# i2c_air_temp_humi_ds18b20_hw2_0.net
KiCad netlist of a schematic drawn in EAGLE
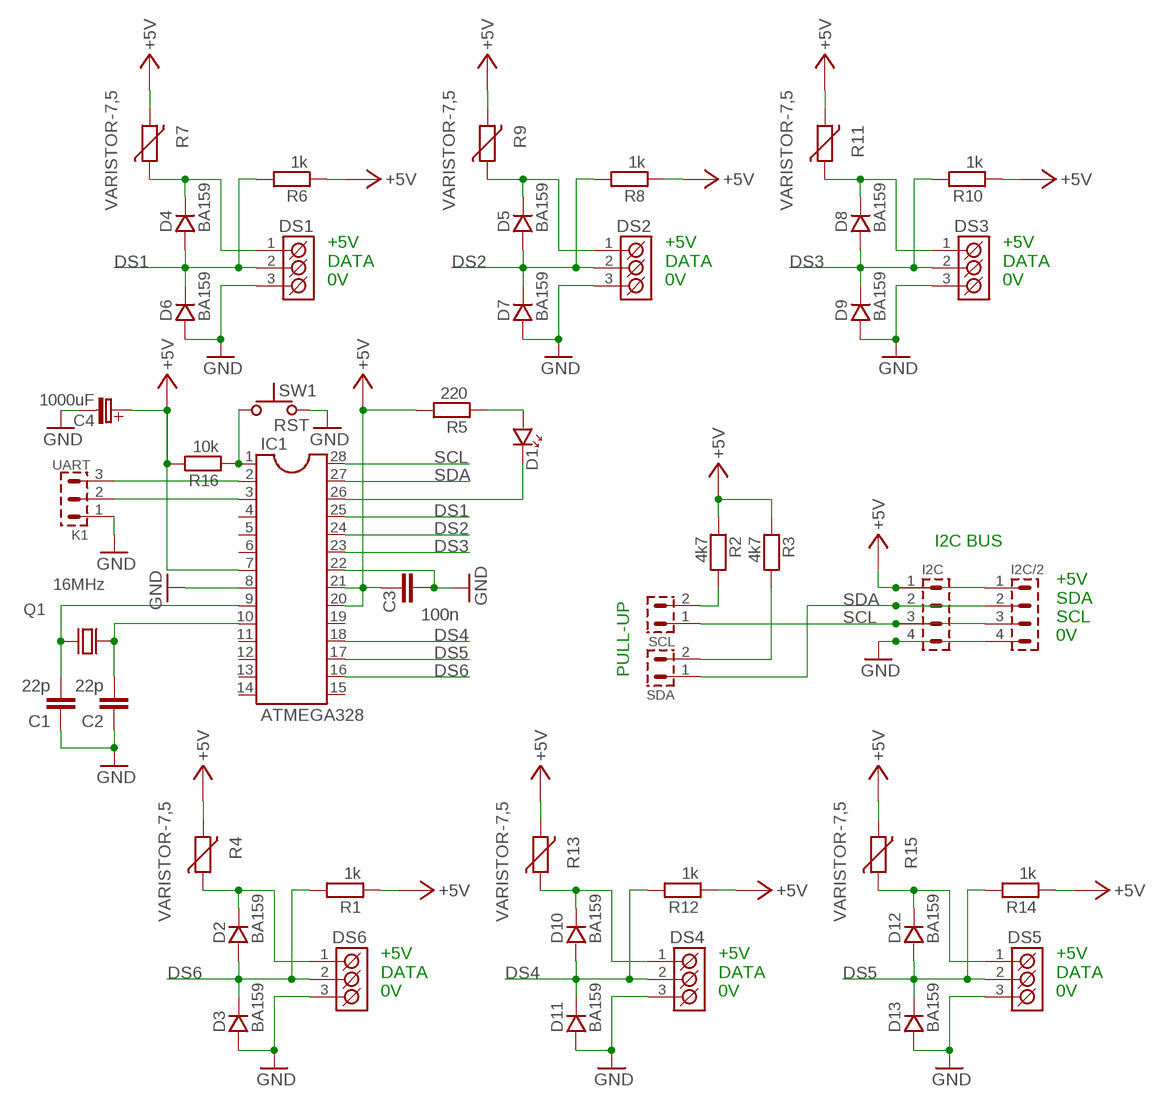
[diagram p0: schematic, sheet 1]

(export (version "E")
  (design (tool "Eeschema 10.0.6"))
  (components
    (comp (ref "C1")
      (value "22p")
      (footprint "eagle-import:C5B3")
      (libsource (lib "eagle-import") (part "C5/3"))
    )
    (comp (ref "C2")
      (value "22p")
      (footprint "eagle-import:C5B3")
      (libsource (lib "eagle-import") (part "C5/3"))
    )
    (comp (ref "C3")
      (value "100n")
      (footprint "eagle-import:C5B3")
      (libsource (lib "eagle-import") (part "C5/3"))
    )
    (comp (ref "C4")
      (value "1000uF")
      (footprint "eagle-import:C-EL_5")
      (libsource (lib "eagle-import") (part "C-EL_5"))
    )
    (comp (ref "D1")
      (value "LED_3")
      (footprint "eagle-import:LED_3")
      (libsource (lib "eagle-import") (part "LED_3"))
    )
    (comp (ref "D2")
      (value "BA159")
      (footprint "eagle-import:DO41")
      (libsource (lib "eagle-import") (part "BA159"))
    )
    (comp (ref "D3")
      (value "BA159")
      (footprint "eagle-import:DO41")
      (libsource (lib "eagle-import") (part "BA159"))
    )
    (comp (ref "D4")
      (value "BA159")
      (footprint "eagle-import:DO41")
      (libsource (lib "eagle-import") (part "BA159"))
    )
    (comp (ref "D5")
      (value "BA159")
      (footprint "eagle-import:DO41")
      (libsource (lib "eagle-import") (part "BA159"))
    )
    (comp (ref "D6")
      (value "BA159")
      (footprint "eagle-import:DO41")
      (libsource (lib "eagle-import") (part "BA159"))
    )
    (comp (ref "D7")
      (value "BA159")
      (footprint "eagle-import:DO41")
      (libsource (lib "eagle-import") (part "BA159"))
    )
    (comp (ref "D8")
      (value "BA159")
      (footprint "eagle-import:DO41")
      (libsource (lib "eagle-import") (part "BA159"))
    )
    (comp (ref "D9")
      (value "BA159")
      (footprint "eagle-import:DO41")
      (libsource (lib "eagle-import") (part "BA159"))
    )
    (comp (ref "D10")
      (value "BA159")
      (footprint "eagle-import:DO41")
      (libsource (lib "eagle-import") (part "BA159"))
    )
    (comp (ref "D11")
      (value "BA159")
      (footprint "eagle-import:DO41")
      (libsource (lib "eagle-import") (part "BA159"))
    )
    (comp (ref "D12")
      (value "BA159")
      (footprint "eagle-import:DO41")
      (libsource (lib "eagle-import") (part "BA159"))
    )
    (comp (ref "D13")
      (value "BA159")
      (footprint "eagle-import:DO41")
      (libsource (lib "eagle-import") (part "BA159"))
    )
    (comp (ref "DS1")
      (value "ARK500/3")
      (footprint "eagle-import:ARK500_3")
      (libsource (lib "eagle-import") (part "ARK500/3"))
    )
    (comp (ref "DS2")
      (value "ARK500/3")
      (footprint "eagle-import:ARK500_3")
      (libsource (lib "eagle-import") (part "ARK500/3"))
    )
    (comp (ref "DS3")
      (value "ARK500/3")
      (footprint "eagle-import:ARK500_3")
      (libsource (lib "eagle-import") (part "ARK500/3"))
    )
    (comp (ref "DS4")
      (value "ARK500/3")
      (footprint "eagle-import:ARK500_3")
      (libsource (lib "eagle-import") (part "ARK500/3"))
    )
    (comp (ref "DS5")
      (value "ARK500/3")
      (footprint "eagle-import:ARK500_3")
      (libsource (lib "eagle-import") (part "ARK500/3"))
    )
    (comp (ref "DS6")
      (value "ARK500/3")
      (footprint "eagle-import:ARK500_3")
      (libsource (lib "eagle-import") (part "ARK500/3"))
    )
    (comp (ref "I2C")
      (value "PSH02-04P")
      (footprint "eagle-import:PSH02-04P")
      (libsource (lib "eagle-import") (part "PSH02-04P"))
    )
    (comp (ref "I2C/2")
      (value "PSH02-04P")
      (footprint "eagle-import:PSH02-04P")
      (libsource (lib "eagle-import") (part "PSH02-04P"))
    )
    (comp (ref "IC1")
      (value "ATMEGA328")
      (footprint "eagle-import:DIL28-3")
      (libsource (lib "eagle-import") (part "DIL28-3"))
    )
    (comp (ref "K1")
      (value "UART")
      (footprint "eagle-import:PSH02-03P")
      (libsource (lib "eagle-import") (part "PSH02-03P"))
    )
    (comp (ref "Q1")
      (value "16MHz")
      (footprint "eagle-import:HC-49U")
      (libsource (lib "eagle-import") (part "Q_HC-49U"))
    )
    (comp (ref "R1")
      (value "1k")
      (footprint "eagle-import:R-7,5")
      (libsource (lib "eagle-import") (part "R_7,5"))
    )
    (comp (ref "R2")
      (value "4k7")
      (footprint "eagle-import:R-7,5")
      (libsource (lib "eagle-import") (part "R_7,5"))
    )
    (comp (ref "R3")
      (value "4k7")
      (footprint "eagle-import:R-7,5")
      (libsource (lib "eagle-import") (part "R_7,5"))
    )
    (comp (ref "R4")
      (value "VARISTOR-7,5")
      (footprint "eagle-import:R-7,5")
      (libsource (lib "eagle-import") (part "VARISTOR-7,5"))
    )
    (comp (ref "R5")
      (value "220")
      (footprint "eagle-import:R-7,5")
      (libsource (lib "eagle-import") (part "R_7,5"))
    )
    (comp (ref "R6")
      (value "1k")
      (footprint "eagle-import:R-7,5")
      (libsource (lib "eagle-import") (part "R_7,5"))
    )
    (comp (ref "R7")
      (value "VARISTOR-7,5")
      (footprint "eagle-import:R-7,5")
      (libsource (lib "eagle-import") (part "VARISTOR-7,5"))
    )
    (comp (ref "R8")
      (value "1k")
      (footprint "eagle-import:R-7,5")
      (libsource (lib "eagle-import") (part "R_7,5"))
    )
    (comp (ref "R9")
      (value "VARISTOR-7,5")
      (footprint "eagle-import:R-7,5")
      (libsource (lib "eagle-import") (part "VARISTOR-7,5"))
    )
    (comp (ref "R10")
      (value "1k")
      (footprint "eagle-import:R-7,5")
      (libsource (lib "eagle-import") (part "R_7,5"))
    )
    (comp (ref "R11")
      (value "VARISTOR-7,5")
      (footprint "eagle-import:R-7,5")
      (libsource (lib "eagle-import") (part "VARISTOR-7,5"))
    )
    (comp (ref "R12")
      (value "1k")
      (footprint "eagle-import:R-7,5")
      (libsource (lib "eagle-import") (part "R_7,5"))
    )
    (comp (ref "R13")
      (value "VARISTOR-7,5")
      (footprint "eagle-import:R-7,5")
      (libsource (lib "eagle-import") (part "VARISTOR-7,5"))
    )
    (comp (ref "R14")
      (value "1k")
      (footprint "eagle-import:R-7,5")
      (libsource (lib "eagle-import") (part "R_7,5"))
    )
    (comp (ref "R15")
      (value "VARISTOR-7,5")
      (footprint "eagle-import:R-7,5")
      (libsource (lib "eagle-import") (part "VARISTOR-7,5"))
    )
    (comp (ref "R16")
      (value "10k")
      (footprint "eagle-import:R-7,5")
      (libsource (lib "eagle-import") (part "R_7,5"))
    )
    (comp (ref "SCL")
      (value "S1G2_JUMP")
      (footprint "eagle-import:S1G2_JUM")
      (libsource (lib "eagle-import") (part "S1G2_JUMP"))
    )
    (comp (ref "SDA")
      (value "S1G2_JUMP")
      (footprint "eagle-import:S1G2_JUM")
      (libsource (lib "eagle-import") (part "S1G2_JUMP"))
    )
    (comp (ref "SW1")
      (value "RST")
      (footprint "eagle-import:P-B1720")
      (libsource (lib "eagle-import") (part "P-B1720"))
    )
  )
  (nets
    (net (code "1") (name "+5V") (class "Default")
      (node (ref "C3") (pin "1") (pinfunction "1_1") (pintype "passive"))
      (node (ref "C4") (pin "C+") (pinfunction "C_EL+_C+") (pintype "passive"))
      (node (ref "I2C") (pin "1") (pinfunction "1_1") (pintype "passive"))
      (node (ref "I2C/2") (pin "1") (pinfunction "1_1") (pintype "passive"))
      (node (ref "IC1") (pin "20") (pinfunction "20_20") (pintype "passive"))
      (node (ref "IC1") (pin "21") (pinfunction "21_21") (pintype "passive"))
      (node (ref "IC1") (pin "7") (pinfunction "7_7") (pintype "passive"))
      (node (ref "R1") (pin "1") (pinfunction "1_1") (pintype "passive"))
      (node (ref "R10") (pin "1") (pinfunction "1_1") (pintype "passive"))
      (node (ref "R11") (pin "2") (pinfunction "2_2") (pintype "passive"))
      (node (ref "R12") (pin "1") (pinfunction "1_1") (pintype "passive"))
      (node (ref "R13") (pin "2") (pinfunction "2_2") (pintype "passive"))
      (node (ref "R14") (pin "1") (pinfunction "1_1") (pintype "passive"))
      (node (ref "R15") (pin "2") (pinfunction "2_2") (pintype "passive"))
      (node (ref "R16") (pin "2") (pinfunction "2_2") (pintype "passive"))
      (node (ref "R2") (pin "1") (pinfunction "1_1") (pintype "passive"))
      (node (ref "R3") (pin "1") (pinfunction "1_1") (pintype "passive"))
      (node (ref "R4") (pin "2") (pinfunction "2_2") (pintype "passive"))
      (node (ref "R5") (pin "2") (pinfunction "2_2") (pintype "passive"))
      (node (ref "R6") (pin "1") (pinfunction "1_1") (pintype "passive"))
      (node (ref "R7") (pin "2") (pinfunction "2_2") (pintype "passive"))
      (node (ref "R8") (pin "1") (pinfunction "1_1") (pintype "passive"))
      (node (ref "R9") (pin "2") (pinfunction "2_2") (pintype "passive"))
    )
    (net (code "2") (name "/DS1") (class "Default")
      (node (ref "D4") (pin "A") (pinfunction "A_A") (pintype "passive"))
      (node (ref "D6") (pin "K") (pinfunction "K_K") (pintype "passive"))
      (node (ref "DS1") (pin "2") (pinfunction "K2_2") (pintype "passive"))
      (node (ref "IC1") (pin "25") (pinfunction "25_25") (pintype "passive"))
      (node (ref "R6") (pin "2") (pinfunction "2_2") (pintype "passive"))
    )
    (net (code "3") (name "/DS2") (class "Default")
      (node (ref "D5") (pin "A") (pinfunction "A_A") (pintype "passive"))
      (node (ref "D7") (pin "K") (pinfunction "K_K") (pintype "passive"))
      (node (ref "DS2") (pin "2") (pinfunction "K2_2") (pintype "passive"))
      (node (ref "IC1") (pin "24") (pinfunction "24_24") (pintype "passive"))
      (node (ref "R8") (pin "2") (pinfunction "2_2") (pintype "passive"))
    )
    (net (code "4") (name "/DS3") (class "Default")
      (node (ref "D8") (pin "A") (pinfunction "A_A") (pintype "passive"))
      (node (ref "D9") (pin "K") (pinfunction "K_K") (pintype "passive"))
      (node (ref "DS3") (pin "2") (pinfunction "K2_2") (pintype "passive"))
      (node (ref "IC1") (pin "23") (pinfunction "23_23") (pintype "passive"))
      (node (ref "R10") (pin "2") (pinfunction "2_2") (pintype "passive"))
    )
    (net (code "5") (name "/DS4") (class "Default")
      (node (ref "D10") (pin "A") (pinfunction "A_A") (pintype "passive"))
      (node (ref "D11") (pin "K") (pinfunction "K_K") (pintype "passive"))
      (node (ref "DS4") (pin "2") (pinfunction "K2_2") (pintype "passive"))
      (node (ref "IC1") (pin "18") (pinfunction "18_18") (pintype "passive"))
      (node (ref "R12") (pin "2") (pinfunction "2_2") (pintype "passive"))
    )
    (net (code "6") (name "/DS5") (class "Default")
      (node (ref "D12") (pin "A") (pinfunction "A_A") (pintype "passive"))
      (node (ref "D13") (pin "K") (pinfunction "K_K") (pintype "passive"))
      (node (ref "DS5") (pin "2") (pinfunction "K2_2") (pintype "passive"))
      (node (ref "IC1") (pin "17") (pinfunction "17_17") (pintype "passive"))
      (node (ref "R14") (pin "2") (pinfunction "2_2") (pintype "passive"))
    )
    (net (code "7") (name "/DS6") (class "Default")
      (node (ref "D2") (pin "A") (pinfunction "A_A") (pintype "passive"))
      (node (ref "D3") (pin "K") (pinfunction "K_K") (pintype "passive"))
      (node (ref "DS6") (pin "2") (pinfunction "K2_2") (pintype "passive"))
      (node (ref "IC1") (pin "16") (pinfunction "16_16") (pintype "passive"))
      (node (ref "R1") (pin "2") (pinfunction "2_2") (pintype "passive"))
    )
    (net (code "8") (name "/SCL") (class "Default")
      (node (ref "I2C") (pin "3") (pinfunction "3_3") (pintype "passive"))
      (node (ref "I2C/2") (pin "3") (pinfunction "3_3") (pintype "passive"))
      (node (ref "IC1") (pin "28") (pinfunction "28_28") (pintype "passive"))
      (node (ref "SCL") (pin "1") (pinfunction "1_1") (pintype "passive"))
    )
    (net (code "9") (name "/SDA") (class "Default")
      (node (ref "I2C") (pin "2") (pinfunction "2_2") (pintype "passive"))
      (node (ref "I2C/2") (pin "2") (pinfunction "2_2") (pintype "passive"))
      (node (ref "IC1") (pin "27") (pinfunction "27_27") (pintype "passive"))
      (node (ref "SDA") (pin "1") (pinfunction "1_1") (pintype "passive"))
    )
    (net (code "10") (name "GND") (class "Default")
      (node (ref "C1") (pin "1") (pinfunction "1_1") (pintype "passive"))
      (node (ref "C2") (pin "1") (pinfunction "1_1") (pintype "passive"))
      (node (ref "C3") (pin "2") (pinfunction "2_2") (pintype "passive"))
      (node (ref "C4") (pin "C-") (pinfunction "C_EL-_C-") (pintype "passive"))
      (node (ref "D11") (pin "A") (pinfunction "A_A") (pintype "passive"))
      (node (ref "D13") (pin "A") (pinfunction "A_A") (pintype "passive"))
      (node (ref "D3") (pin "A") (pinfunction "A_A") (pintype "passive"))
      (node (ref "D6") (pin "A") (pinfunction "A_A") (pintype "passive"))
      (node (ref "D7") (pin "A") (pinfunction "A_A") (pintype "passive"))
      (node (ref "D9") (pin "A") (pinfunction "A_A") (pintype "passive"))
      (node (ref "DS1") (pin "3") (pinfunction "K3_3") (pintype "passive"))
      (node (ref "DS2") (pin "3") (pinfunction "K3_3") (pintype "passive"))
      (node (ref "DS3") (pin "3") (pinfunction "K3_3") (pintype "passive"))
      (node (ref "DS4") (pin "3") (pinfunction "K3_3") (pintype "passive"))
      (node (ref "DS5") (pin "3") (pinfunction "K3_3") (pintype "passive"))
      (node (ref "DS6") (pin "3") (pinfunction "K3_3") (pintype "passive"))
      (node (ref "I2C") (pin "4") (pinfunction "4_4") (pintype "passive"))
      (node (ref "I2C/2") (pin "4") (pinfunction "4_4") (pintype "passive"))
      (node (ref "IC1") (pin "22") (pinfunction "22_22") (pintype "passive"))
      (node (ref "IC1") (pin "8") (pinfunction "8_8") (pintype "passive"))
      (node (ref "K1") (pin "1") (pinfunction "1_1") (pintype "passive"))
      (node (ref "SW1") (pin "2") (pinfunction "2_2") (pintype "passive"))
    )
    (net (code "11") (name "Net-(C1-Pad2)") (class "Default")
      (node (ref "C1") (pin "2") (pinfunction "2_2") (pintype "passive"))
      (node (ref "IC1") (pin "9") (pinfunction "9_9") (pintype "passive"))
      (node (ref "Q1") (pin "2") (pinfunction "2_2") (pintype "passive"))
    )
    (net (code "12") (name "Net-(C2-Pad2)") (class "Default")
      (node (ref "C2") (pin "2") (pinfunction "2_2") (pintype "passive"))
      (node (ref "IC1") (pin "10") (pinfunction "10_10") (pintype "passive"))
      (node (ref "Q1") (pin "1") (pinfunction "1_1") (pintype "passive"))
    )
    (net (code "13") (name "Net-(D1-PadA)") (class "Default")
      (node (ref "D1") (pin "A") (pinfunction "A_A") (pintype "passive"))
      (node (ref "R5") (pin "1") (pinfunction "1_1") (pintype "passive"))
    )
    (net (code "14") (name "Net-(D1-PadK)") (class "Default")
      (node (ref "D1") (pin "K") (pinfunction "K_K") (pintype "passive"))
      (node (ref "IC1") (pin "26") (pinfunction "26_26") (pintype "passive"))
    )
    (net (code "15") (name "Net-(DS1-K1)") (class "Default")
      (node (ref "D4") (pin "K") (pinfunction "K_K") (pintype "passive"))
      (node (ref "DS1") (pin "1") (pinfunction "K1_1") (pintype "passive"))
      (node (ref "R7") (pin "1") (pinfunction "1_1") (pintype "passive"))
    )
    (net (code "16") (name "Net-(DS2-K1)") (class "Default")
      (node (ref "D5") (pin "K") (pinfunction "K_K") (pintype "passive"))
      (node (ref "DS2") (pin "1") (pinfunction "K1_1") (pintype "passive"))
      (node (ref "R9") (pin "1") (pinfunction "1_1") (pintype "passive"))
    )
    (net (code "17") (name "Net-(DS3-K1)") (class "Default")
      (node (ref "D8") (pin "K") (pinfunction "K_K") (pintype "passive"))
      (node (ref "DS3") (pin "1") (pinfunction "K1_1") (pintype "passive"))
      (node (ref "R11") (pin "1") (pinfunction "1_1") (pintype "passive"))
    )
    (net (code "18") (name "Net-(DS4-K1)") (class "Default")
      (node (ref "D10") (pin "K") (pinfunction "K_K") (pintype "passive"))
      (node (ref "DS4") (pin "1") (pinfunction "K1_1") (pintype "passive"))
      (node (ref "R13") (pin "1") (pinfunction "1_1") (pintype "passive"))
    )
    (net (code "19") (name "Net-(DS5-K1)") (class "Default")
      (node (ref "D12") (pin "K") (pinfunction "K_K") (pintype "passive"))
      (node (ref "DS5") (pin "1") (pinfunction "K1_1") (pintype "passive"))
      (node (ref "R15") (pin "1") (pinfunction "1_1") (pintype "passive"))
    )
    (net (code "20") (name "Net-(DS6-K1)") (class "Default")
      (node (ref "D2") (pin "K") (pinfunction "K_K") (pintype "passive"))
      (node (ref "DS6") (pin "1") (pinfunction "K1_1") (pintype "passive"))
      (node (ref "R4") (pin "1") (pinfunction "1_1") (pintype "passive"))
    )
    (net (code "21") (name "Net-(IC1-Pad1)") (class "Default")
      (node (ref "IC1") (pin "1") (pinfunction "1_1") (pintype "passive"))
      (node (ref "R16") (pin "1") (pinfunction "1_1") (pintype "passive"))
      (node (ref "SW1") (pin "1") (pinfunction "1_1") (pintype "passive"))
    )
    (net (code "22") (name "Net-(IC1-Pad2)") (class "Default")
      (node (ref "IC1") (pin "2") (pinfunction "2_2") (pintype "passive"))
      (node (ref "K1") (pin "3") (pinfunction "3_3") (pintype "passive"))
    )
    (net (code "23") (name "Net-(IC1-Pad3)") (class "Default")
      (node (ref "IC1") (pin "3") (pinfunction "3_3") (pintype "passive"))
      (node (ref "K1") (pin "2") (pinfunction "2_2") (pintype "passive"))
    )
    (net (code "24") (name "Net-(R2-Pad2)") (class "Default")
      (node (ref "R2") (pin "2") (pinfunction "2_2") (pintype "passive"))
      (node (ref "SCL") (pin "2") (pinfunction "2_2") (pintype "passive"))
    )
    (net (code "25") (name "Net-(R3-Pad2)") (class "Default")
      (node (ref "R3") (pin "2") (pinfunction "2_2") (pintype "passive"))
      (node (ref "SDA") (pin "2") (pinfunction "2_2") (pintype "passive"))
    )
    (net (code "26") (name "unconnected-(IC1-Pad4)") (class "Default")
      (node (ref "IC1") (pin "4") (pinfunction "4_4") (pintype "passive"))
    )
    (net (code "27") (name "unconnected-(IC1-Pad5)") (class "Default")
      (node (ref "IC1") (pin "5") (pinfunction "5_5") (pintype "passive"))
    )
    (net (code "28") (name "unconnected-(IC1-Pad6)") (class "Default")
      (node (ref "IC1") (pin "6") (pinfunction "6_6") (pintype "passive"))
    )
    (net (code "29") (name "unconnected-(IC1-Pad11)") (class "Default")
      (node (ref "IC1") (pin "11") (pinfunction "11_11") (pintype "passive"))
    )
    (net (code "30") (name "unconnected-(IC1-Pad12)") (class "Default")
      (node (ref "IC1") (pin "12") (pinfunction "12_12") (pintype "passive"))
    )
    (net (code "31") (name "unconnected-(IC1-Pad13)") (class "Default")
      (node (ref "IC1") (pin "13") (pinfunction "13_13") (pintype "passive"))
    )
    (net (code "32") (name "unconnected-(IC1-Pad14)") (class "Default")
      (node (ref "IC1") (pin "14") (pinfunction "14_14") (pintype "passive"))
    )
    (net (code "33") (name "unconnected-(IC1-Pad15)") (class "Default")
      (node (ref "IC1") (pin "15") (pinfunction "15_15") (pintype "passive"))
    )
    (net (code "34") (name "unconnected-(IC1-Pad19)") (class "Default")
      (node (ref "IC1") (pin "19") (pinfunction "19_19") (pintype "passive"))
    )
    (net (code "35") (name "unconnected-(SW1-1A-Pad3)") (class "Default")
      (node (ref "SW1") (pin "3") (pinfunction "1A_3") (pintype "passive"))
    )
    (net (code "36") (name "unconnected-(SW1-2A-Pad4)") (class "Default")
      (node (ref "SW1") (pin "4") (pinfunction "2A_4") (pintype "passive"))
    )
  )
)
